# 10-M2_GPS.net
KiCad netlist of a schematic drawn in Altium Designer
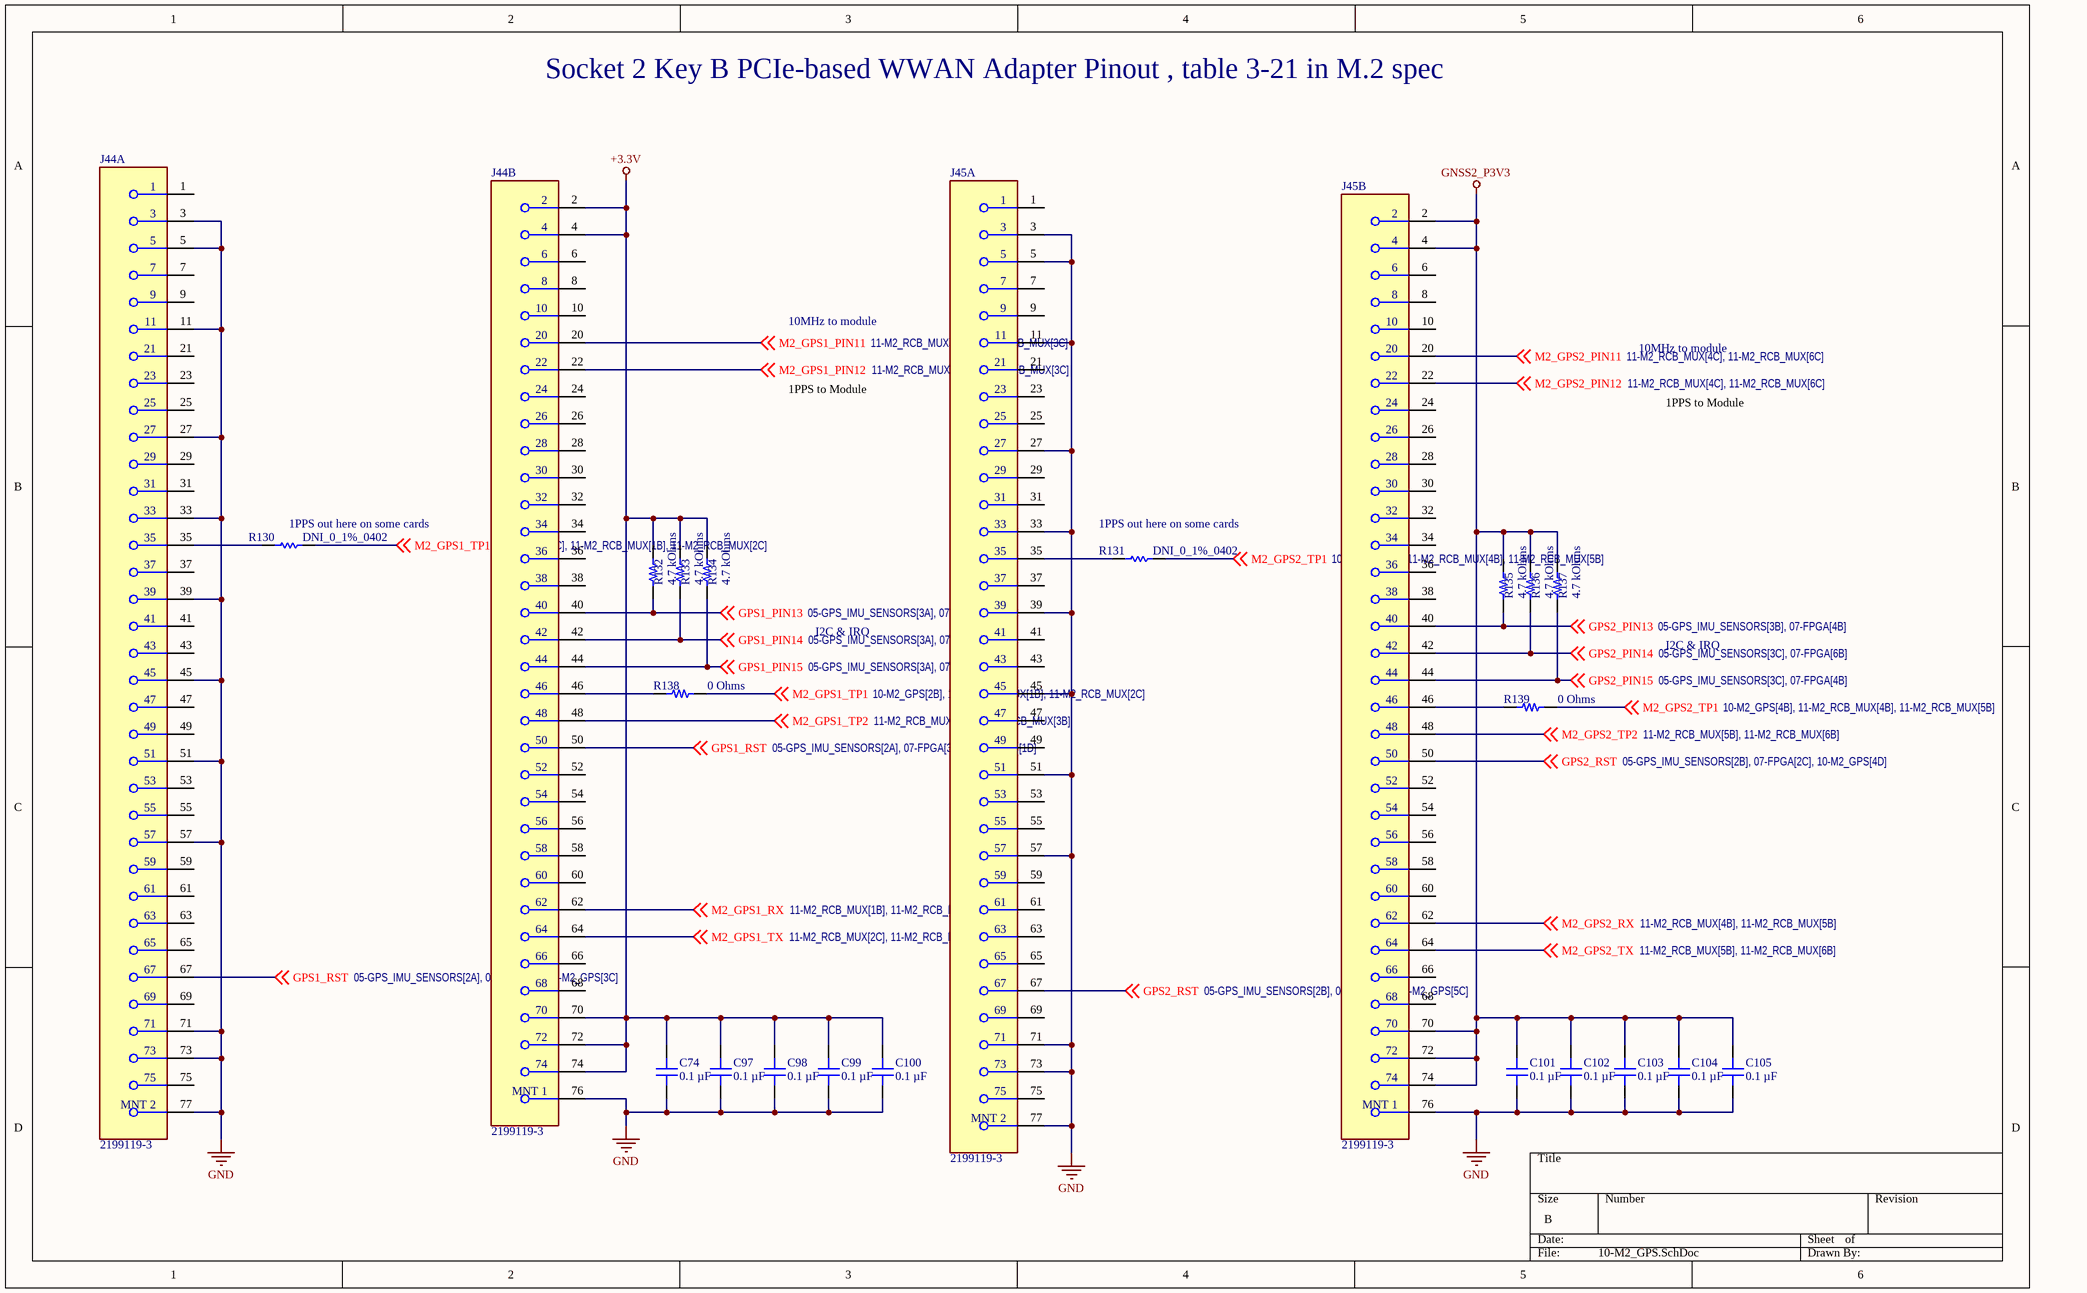
[diagram p0: 10-M2_GPS.SchDoc]

(export (version "E")
  (design (tool "Eeschema 10.0.6"))
  (components
    (comp (ref "C74")
      (value "0.1 µF")
      (footprint "CAP 0402_1005")
      (description "CAP CER 0.1UF 50V X7R 0402")
      (fields (field (name "TOLERANCE") "±10%") (field (name "PART NUMBER") "CC0402KRX7R9BB104"))
      (libsource (lib "Celestial Altium Library - altium_library") (part "Capacitor"))
    )
    (comp (ref "C97")
      (value "0.1 µF")
      (footprint "CAP 0402_1005")
      (description "CAP CER 0.1UF 50V X7R 0402")
      (fields (field (name "TOLERANCE") "±10%") (field (name "PART NUMBER") "CC0402KRX7R9BB104"))
      (libsource (lib "Celestial Altium Library - altium_library") (part "Capacitor"))
    )
    (comp (ref "C98")
      (value "0.1 µF")
      (footprint "CAP 0402_1005")
      (description "CAP CER 0.1UF 50V X7R 0402")
      (fields (field (name "TOLERANCE") "±10%") (field (name "PART NUMBER") "CC0402KRX7R9BB104"))
      (libsource (lib "Celestial Altium Library - altium_library") (part "Capacitor"))
    )
    (comp (ref "C99")
      (value "0.1 µF")
      (footprint "CAP 0402_1005")
      (description "CAP CER 0.1UF 50V X7R 0402")
      (fields (field (name "TOLERANCE") "±10%") (field (name "PART NUMBER") "CC0402KRX7R9BB104"))
      (libsource (lib "Celestial Altium Library - altium_library") (part "Capacitor"))
    )
    (comp (ref "C100")
      (value "0.1 µF")
      (footprint "CAP 0402_1005")
      (description "CAP CER 0.1UF 50V X7R 0402")
      (fields (field (name "TOLERANCE") "±10%") (field (name "PART NUMBER") "CC0402KRX7R9BB104"))
      (libsource (lib "Celestial Altium Library - altium_library") (part "Capacitor"))
    )
    (comp (ref "C101")
      (value "0.1 µF")
      (footprint "CAP 0402_1005")
      (description "CAP CER 0.1UF 50V X7R 0402")
      (fields (field (name "TOLERANCE") "±10%") (field (name "PART NUMBER") "CC0402KRX7R9BB104"))
      (libsource (lib "Celestial Altium Library - altium_library") (part "Capacitor"))
    )
    (comp (ref "C102")
      (value "0.1 µF")
      (footprint "CAP 0402_1005")
      (description "CAP CER 0.1UF 50V X7R 0402")
      (fields (field (name "TOLERANCE") "±10%") (field (name "PART NUMBER") "CC0402KRX7R9BB104"))
      (libsource (lib "Celestial Altium Library - altium_library") (part "Capacitor"))
    )
    (comp (ref "C103")
      (value "0.1 µF")
      (footprint "CAP 0402_1005")
      (description "CAP CER 0.1UF 50V X7R 0402")
      (fields (field (name "TOLERANCE") "±10%") (field (name "PART NUMBER") "CC0402KRX7R9BB104"))
      (libsource (lib "Celestial Altium Library - altium_library") (part "Capacitor"))
    )
    (comp (ref "C104")
      (value "0.1 µF")
      (footprint "CAP 0402_1005")
      (description "CAP CER 0.1UF 50V X7R 0402")
      (fields (field (name "TOLERANCE") "±10%") (field (name "PART NUMBER") "CC0402KRX7R9BB104"))
      (libsource (lib "Celestial Altium Library - altium_library") (part "Capacitor"))
    )
    (comp (ref "C105")
      (value "0.1 µF")
      (footprint "CAP 0402_1005")
      (description "CAP CER 0.1UF 50V X7R 0402")
      (fields (field (name "TOLERANCE") "±10%") (field (name "PART NUMBER") "CC0402KRX7R9BB104"))
      (libsource (lib "Celestial Altium Library - altium_library") (part "Capacitor"))
    )
    (comp (ref "J44")
      (value "2199119-3")
      (footprint "FP-2199119-3-MFG")
      (description "CONN M.2 FEMALE 67POS 0.020 GOLD")
      (libsource (lib "Altium Content Vault") (part "a14843ccfa78e5d0b739856168502fb"))
    )
    (comp (ref "J45")
      (value "2199119-3")
      (footprint "FP-2199119-3-MFG")
      (description "CONN M.2 FEMALE 67POS 0.020 GOLD")
      (libsource (lib "Altium Content Vault") (part "a14843ccfa78e5d0b739856168502fb"))
    )
    (comp (ref "R130")
      (value "DNI_0_1%_0402")
      (footprint "RESC1005X40X25LL05T05")
      (description "Chip Resistor, 0 Ohm, 0.1 W, -55 to 155 degC, 0402 (1005 Metric), RoHS, Tape and Reel")
      (fields (field (name "MANUFACTURER") "Panasonic") (field (name "TOLERANCE") "5%"))
      (libsource (lib "Altium Content Vault") (part "RES-2"))
    )
    (comp (ref "R131")
      (value "DNI_0_1%_0402")
      (footprint "RESC1005X40X25LL05T05")
      (description "Chip Resistor, 0 Ohm, 0.1 W, -55 to 155 degC, 0402 (1005 Metric), RoHS, Tape and Reel")
      (fields (field (name "MANUFACTURER") "Panasonic") (field (name "TOLERANCE") "5%"))
      (libsource (lib "Altium Content Vault") (part "RES-2"))
    )
    (comp (ref "R132")
      (value "4.7 kOhms")
      (footprint "YAGEO RES 0402_1005")
      (description "RES 4.7K OHM 1% 1/16W 0402")
      (fields (field (name "MANUFACTURER") "Yageo") (field (name "PART NUMBER") "RC0402FR-074K7L"))
      (libsource (lib "Celestial Altium Library - altium_library") (part "Resistor"))
    )
    (comp (ref "R133")
      (value "4.7 kOhms")
      (footprint "YAGEO RES 0402_1005")
      (description "RES 4.7K OHM 1% 1/16W 0402")
      (fields (field (name "MANUFACTURER") "Yageo") (field (name "PART NUMBER") "RC0402FR-074K7L"))
      (libsource (lib "Celestial Altium Library - altium_library") (part "Resistor"))
    )
    (comp (ref "R134")
      (value "4.7 kOhms")
      (footprint "YAGEO RES 0402_1005")
      (description "RES 4.7K OHM 1% 1/16W 0402")
      (fields (field (name "MANUFACTURER") "Yageo") (field (name "PART NUMBER") "RC0402FR-074K7L"))
      (libsource (lib "Celestial Altium Library - altium_library") (part "Resistor"))
    )
    (comp (ref "R135")
      (value "4.7 kOhms")
      (footprint "YAGEO RES 0402_1005")
      (description "RES 4.7K OHM 1% 1/16W 0402")
      (fields (field (name "MANUFACTURER") "Yageo") (field (name "PART NUMBER") "RC0402FR-074K7L"))
      (libsource (lib "Celestial Altium Library - altium_library") (part "Resistor"))
    )
    (comp (ref "R136")
      (value "4.7 kOhms")
      (footprint "YAGEO RES 0402_1005")
      (description "RES 4.7K OHM 1% 1/16W 0402")
      (fields (field (name "MANUFACTURER") "Yageo") (field (name "PART NUMBER") "RC0402FR-074K7L"))
      (libsource (lib "Celestial Altium Library - altium_library") (part "Resistor"))
    )
    (comp (ref "R137")
      (value "4.7 kOhms")
      (footprint "YAGEO RES 0402_1005")
      (description "RES 4.7K OHM 1% 1/16W 0402")
      (fields (field (name "MANUFACTURER") "Yageo") (field (name "PART NUMBER") "RC0402FR-074K7L"))
      (libsource (lib "Celestial Altium Library - altium_library") (part "Resistor"))
    )
    (comp (ref "R138")
      (value "0 Ohms")
      (footprint "YAGEO RES 0402_1005")
      (description "RES 0 OHM JUMPER 1/16W 0402")
      (fields (field (name "MANUFACTURER") "Yageo") (field (name "TOLERANCE") "Jumper"))
      (libsource (lib "Celestial Altium Library - altium_library") (part "Resistor"))
    )
    (comp (ref "R139")
      (value "0 Ohms")
      (footprint "YAGEO RES 0402_1005")
      (description "RES 0 OHM JUMPER 1/16W 0402")
      (fields (field (name "MANUFACTURER") "Yageo") (field (name "TOLERANCE") "Jumper"))
      (libsource (lib "Celestial Altium Library - altium_library") (part "Resistor"))
    )
  )
  (nets
    (net (code "1") (name "+3.3V") (class "Default")
      (node (ref "C100") (pin "1") (pinfunction "1_1") (pintype "passive"))
      (node (ref "C74") (pin "1") (pinfunction "1_1") (pintype "passive"))
      (node (ref "C97") (pin "1") (pinfunction "1_1") (pintype "passive"))
      (node (ref "C98") (pin "1") (pinfunction "1_1") (pintype "passive"))
      (node (ref "C99") (pin "1") (pinfunction "1_1") (pintype "passive"))
      (node (ref "J44") (pin "2") (pinfunction "2_2") (pintype "passive"))
      (node (ref "J44") (pin "4") (pinfunction "4_4") (pintype "passive"))
      (node (ref "J44") (pin "70") (pinfunction "70_70") (pintype "passive"))
      (node (ref "J44") (pin "72") (pinfunction "72_72") (pintype "passive"))
      (node (ref "J44") (pin "74") (pinfunction "74_74") (pintype "passive"))
      (node (ref "R132") (pin "2") (pinfunction "2_2") (pintype "passive"))
      (node (ref "R133") (pin "2") (pinfunction "2_2") (pintype "passive"))
      (node (ref "R134") (pin "2") (pinfunction "2_2") (pintype "passive"))
    )
    (net (code "2") (name "GND") (class "Default")
      (node (ref "C100") (pin "2") (pinfunction "2_2") (pintype "passive"))
      (node (ref "C101") (pin "2") (pinfunction "2_2") (pintype "passive"))
      (node (ref "C102") (pin "2") (pinfunction "2_2") (pintype "passive"))
      (node (ref "C103") (pin "2") (pinfunction "2_2") (pintype "passive"))
      (node (ref "C104") (pin "2") (pinfunction "2_2") (pintype "passive"))
      (node (ref "C105") (pin "2") (pinfunction "2_2") (pintype "passive"))
      (node (ref "C74") (pin "2") (pinfunction "2_2") (pintype "passive"))
      (node (ref "C97") (pin "2") (pinfunction "2_2") (pintype "passive"))
      (node (ref "C98") (pin "2") (pinfunction "2_2") (pintype "passive"))
      (node (ref "C99") (pin "2") (pinfunction "2_2") (pintype "passive"))
      (node (ref "J44") (pin "11") (pinfunction "11_11") (pintype "passive"))
      (node (ref "J44") (pin "27") (pinfunction "27_27") (pintype "passive"))
      (node (ref "J44") (pin "3") (pinfunction "3_3") (pintype "passive"))
      (node (ref "J44") (pin "33") (pinfunction "33_33") (pintype "passive"))
      (node (ref "J44") (pin "39") (pinfunction "39_39") (pintype "passive"))
      (node (ref "J44") (pin "45") (pinfunction "45_45") (pintype "passive"))
      (node (ref "J44") (pin "5") (pinfunction "5_5") (pintype "passive"))
      (node (ref "J44") (pin "51") (pinfunction "51_51") (pintype "passive"))
      (node (ref "J44") (pin "57") (pinfunction "57_57") (pintype "passive"))
      (node (ref "J44") (pin "71") (pinfunction "71_71") (pintype "passive"))
      (node (ref "J44") (pin "73") (pinfunction "73_73") (pintype "passive"))
      (node (ref "J44") (pin "76") (pinfunction "MNT_1_76") (pintype "passive"))
      (node (ref "J44") (pin "77") (pinfunction "MNT_2_77") (pintype "passive"))
      (node (ref "J45") (pin "11") (pinfunction "11_11") (pintype "passive"))
      (node (ref "J45") (pin "27") (pinfunction "27_27") (pintype "passive"))
      (node (ref "J45") (pin "3") (pinfunction "3_3") (pintype "passive"))
      (node (ref "J45") (pin "33") (pinfunction "33_33") (pintype "passive"))
      (node (ref "J45") (pin "39") (pinfunction "39_39") (pintype "passive"))
      (node (ref "J45") (pin "45") (pinfunction "45_45") (pintype "passive"))
      (node (ref "J45") (pin "5") (pinfunction "5_5") (pintype "passive"))
      (node (ref "J45") (pin "51") (pinfunction "51_51") (pintype "passive"))
      (node (ref "J45") (pin "57") (pinfunction "57_57") (pintype "passive"))
      (node (ref "J45") (pin "71") (pinfunction "71_71") (pintype "passive"))
      (node (ref "J45") (pin "73") (pinfunction "73_73") (pintype "passive"))
      (node (ref "J45") (pin "76") (pinfunction "MNT_1_76") (pintype "passive"))
      (node (ref "J45") (pin "77") (pinfunction "MNT_2_77") (pintype "passive"))
    )
    (net (code "3") (name "GNSS2_P3V3") (class "Default")
      (node (ref "C101") (pin "1") (pinfunction "1_1") (pintype "passive"))
      (node (ref "C102") (pin "1") (pinfunction "1_1") (pintype "passive"))
      (node (ref "C103") (pin "1") (pinfunction "1_1") (pintype "passive"))
      (node (ref "C104") (pin "1") (pinfunction "1_1") (pintype "passive"))
      (node (ref "C105") (pin "1") (pinfunction "1_1") (pintype "passive"))
      (node (ref "J45") (pin "2") (pinfunction "2_2") (pintype "passive"))
      (node (ref "J45") (pin "4") (pinfunction "4_4") (pintype "passive"))
      (node (ref "J45") (pin "70") (pinfunction "70_70") (pintype "passive"))
      (node (ref "J45") (pin "72") (pinfunction "72_72") (pintype "passive"))
      (node (ref "J45") (pin "74") (pinfunction "74_74") (pintype "passive"))
      (node (ref "R135") (pin "2") (pinfunction "2_2") (pintype "passive"))
      (node (ref "R136") (pin "2") (pinfunction "2_2") (pintype "passive"))
      (node (ref "R137") (pin "2") (pinfunction "2_2") (pintype "passive"))
    )
    (net (code "4") (name "GPS1_PIN13") (class "Default")
      (node (ref "J44") (pin "40") (pinfunction "40_40") (pintype "passive"))
      (node (ref "R132") (pin "1") (pinfunction "1_1") (pintype "passive"))
    )
    (net (code "5") (name "GPS1_PIN14") (class "Default")
      (node (ref "J44") (pin "42") (pinfunction "42_42") (pintype "passive"))
      (node (ref "R133") (pin "1") (pinfunction "1_1") (pintype "passive"))
    )
    (net (code "6") (name "GPS1_PIN15") (class "Default")
      (node (ref "J44") (pin "44") (pinfunction "44_44") (pintype "passive"))
      (node (ref "R134") (pin "1") (pinfunction "1_1") (pintype "passive"))
    )
    (net (code "7") (name "GPS1_RST") (class "Default")
      (node (ref "J44") (pin "50") (pinfunction "50_50") (pintype "passive"))
      (node (ref "J44") (pin "67") (pinfunction "67_67") (pintype "passive"))
    )
    (net (code "8") (name "GPS2_PIN13") (class "Default")
      (node (ref "J45") (pin "40") (pinfunction "40_40") (pintype "passive"))
      (node (ref "R135") (pin "1") (pinfunction "1_1") (pintype "passive"))
    )
    (net (code "9") (name "GPS2_PIN14") (class "Default")
      (node (ref "J45") (pin "42") (pinfunction "42_42") (pintype "passive"))
      (node (ref "R136") (pin "1") (pinfunction "1_1") (pintype "passive"))
    )
    (net (code "10") (name "GPS2_PIN15") (class "Default")
      (node (ref "J45") (pin "44") (pinfunction "44_44") (pintype "passive"))
      (node (ref "R137") (pin "1") (pinfunction "1_1") (pintype "passive"))
    )
    (net (code "11") (name "GPS2_RST") (class "Default")
      (node (ref "J45") (pin "50") (pinfunction "50_50") (pintype "passive"))
      (node (ref "J45") (pin "67") (pinfunction "67_67") (pintype "passive"))
    )
    (net (code "12") (name "M2_GPS1_PIN11") (class "Default")
      (node (ref "J44") (pin "20") (pinfunction "20_20") (pintype "passive"))
    )
    (net (code "13") (name "M2_GPS1_PIN12") (class "Default")
      (node (ref "J44") (pin "22") (pinfunction "22_22") (pintype "passive"))
    )
    (net (code "14") (name "M2_GPS1_RX") (class "Default")
      (node (ref "J44") (pin "62") (pinfunction "62_62") (pintype "passive"))
    )
    (net (code "15") (name "M2_GPS1_TP1") (class "Default")
      (node (ref "R130") (pin "2") (pinfunction "2_2") (pintype "passive"))
      (node (ref "R138") (pin "2") (pinfunction "2_2") (pintype "passive"))
    )
    (net (code "16") (name "M2_GPS1_TP2") (class "Default")
      (node (ref "J44") (pin "48") (pinfunction "48_48") (pintype "passive"))
    )
    (net (code "17") (name "M2_GPS1_TX") (class "Default")
      (node (ref "J44") (pin "64") (pinfunction "64_64") (pintype "passive"))
    )
    (net (code "18") (name "M2_GPS2_PIN11") (class "Default")
      (node (ref "J45") (pin "20") (pinfunction "20_20") (pintype "passive"))
    )
    (net (code "19") (name "M2_GPS2_PIN12") (class "Default")
      (node (ref "J45") (pin "22") (pinfunction "22_22") (pintype "passive"))
    )
    (net (code "20") (name "M2_GPS2_RX") (class "Default")
      (node (ref "J45") (pin "62") (pinfunction "62_62") (pintype "passive"))
    )
    (net (code "21") (name "M2_GPS2_TP1") (class "Default")
      (node (ref "R131") (pin "2") (pinfunction "2_2") (pintype "passive"))
      (node (ref "R139") (pin "2") (pinfunction "2_2") (pintype "passive"))
    )
    (net (code "22") (name "M2_GPS2_TP2") (class "Default")
      (node (ref "J45") (pin "48") (pinfunction "48_48") (pintype "passive"))
    )
    (net (code "23") (name "M2_GPS2_TX") (class "Default")
      (node (ref "J45") (pin "64") (pinfunction "64_64") (pintype "passive"))
    )
    (net (code "24") (name "Net-(J44-Pad35)") (class "Default")
      (node (ref "J44") (pin "35") (pinfunction "35_35") (pintype "passive"))
      (node (ref "R130") (pin "1") (pinfunction "1_1") (pintype "passive"))
    )
    (net (code "25") (name "Net-(J44-Pad46)") (class "Default")
      (node (ref "J44") (pin "46") (pinfunction "46_46") (pintype "passive"))
      (node (ref "R138") (pin "1") (pinfunction "1_1") (pintype "passive"))
    )
    (net (code "26") (name "Net-(J45-Pad35)") (class "Default")
      (node (ref "J45") (pin "35") (pinfunction "35_35") (pintype "passive"))
      (node (ref "R131") (pin "1") (pinfunction "1_1") (pintype "passive"))
    )
    (net (code "27") (name "Net-(J45-Pad46)") (class "Default")
      (node (ref "J45") (pin "46") (pinfunction "46_46") (pintype "passive"))
      (node (ref "R139") (pin "1") (pinfunction "1_1") (pintype "passive"))
    )
    (net (code "28") (name "unconnected-(J44-Pad1)") (class "Default")
      (node (ref "J44") (pin "1") (pinfunction "1_1") (pintype "passive"))
    )
    (net (code "29") (name "unconnected-(J44-Pad6)") (class "Default")
      (node (ref "J44") (pin "6") (pinfunction "6_6") (pintype "passive"))
    )
    (net (code "30") (name "unconnected-(J44-Pad7)") (class "Default")
      (node (ref "J44") (pin "7") (pinfunction "7_7") (pintype "passive"))
    )
    (net (code "31") (name "unconnected-(J44-Pad8)") (class "Default")
      (node (ref "J44") (pin "8") (pinfunction "8_8") (pintype "passive"))
    )
    (net (code "32") (name "unconnected-(J44-Pad9)") (class "Default")
      (node (ref "J44") (pin "9") (pinfunction "9_9") (pintype "passive"))
    )
    (net (code "33") (name "unconnected-(J44-Pad10)") (class "Default")
      (node (ref "J44") (pin "10") (pinfunction "10_10") (pintype "passive"))
    )
    (net (code "34") (name "unconnected-(J44-Pad21)") (class "Default")
      (node (ref "J44") (pin "21") (pinfunction "21_21") (pintype "passive"))
    )
    (net (code "35") (name "unconnected-(J44-Pad23)") (class "Default")
      (node (ref "J44") (pin "23") (pinfunction "23_23") (pintype "passive"))
    )
    (net (code "36") (name "unconnected-(J44-Pad24)") (class "Default")
      (node (ref "J44") (pin "24") (pinfunction "24_24") (pintype "passive"))
    )
    (net (code "37") (name "unconnected-(J44-Pad25)") (class "Default")
      (node (ref "J44") (pin "25") (pinfunction "25_25") (pintype "passive"))
    )
    (net (code "38") (name "unconnected-(J44-Pad26)") (class "Default")
      (node (ref "J44") (pin "26") (pinfunction "26_26") (pintype "passive"))
    )
    (net (code "39") (name "unconnected-(J44-Pad28)") (class "Default")
      (node (ref "J44") (pin "28") (pinfunction "28_28") (pintype "passive"))
    )
    (net (code "40") (name "unconnected-(J44-Pad29)") (class "Default")
      (node (ref "J44") (pin "29") (pinfunction "29_29") (pintype "passive"))
    )
    (net (code "41") (name "unconnected-(J44-Pad30)") (class "Default")
      (node (ref "J44") (pin "30") (pinfunction "30_30") (pintype "passive"))
    )
    (net (code "42") (name "unconnected-(J44-Pad31)") (class "Default")
      (node (ref "J44") (pin "31") (pinfunction "31_31") (pintype "passive"))
    )
    (net (code "43") (name "unconnected-(J44-Pad32)") (class "Default")
      (node (ref "J44") (pin "32") (pinfunction "32_32") (pintype "passive"))
    )
    (net (code "44") (name "unconnected-(J44-Pad34)") (class "Default")
      (node (ref "J44") (pin "34") (pinfunction "34_34") (pintype "passive"))
    )
    (net (code "45") (name "unconnected-(J44-Pad36)") (class "Default")
      (node (ref "J44") (pin "36") (pinfunction "36_36") (pintype "passive"))
    )
    (net (code "46") (name "unconnected-(J44-Pad37)") (class "Default")
      (node (ref "J44") (pin "37") (pinfunction "37_37") (pintype "passive"))
    )
    (net (code "47") (name "unconnected-(J44-Pad38)") (class "Default")
      (node (ref "J44") (pin "38") (pinfunction "38_38") (pintype "passive"))
    )
    (net (code "48") (name "unconnected-(J44-Pad41)") (class "Default")
      (node (ref "J44") (pin "41") (pinfunction "41_41") (pintype "passive"))
    )
    (net (code "49") (name "unconnected-(J44-Pad43)") (class "Default")
      (node (ref "J44") (pin "43") (pinfunction "43_43") (pintype "passive"))
    )
    (net (code "50") (name "unconnected-(J44-Pad47)") (class "Default")
      (node (ref "J44") (pin "47") (pinfunction "47_47") (pintype "passive"))
    )
    (net (code "51") (name "unconnected-(J44-Pad49)") (class "Default")
      (node (ref "J44") (pin "49") (pinfunction "49_49") (pintype "passive"))
    )
    (net (code "52") (name "unconnected-(J44-Pad52)") (class "Default")
      (node (ref "J44") (pin "52") (pinfunction "52_52") (pintype "passive"))
    )
    (net (code "53") (name "unconnected-(J44-Pad53)") (class "Default")
      (node (ref "J44") (pin "53") (pinfunction "53_53") (pintype "passive"))
    )
    (net (code "54") (name "unconnected-(J44-Pad54)") (class "Default")
      (node (ref "J44") (pin "54") (pinfunction "54_54") (pintype "passive"))
    )
    (net (code "55") (name "unconnected-(J44-Pad55)") (class "Default")
      (node (ref "J44") (pin "55") (pinfunction "55_55") (pintype "passive"))
    )
    (net (code "56") (name "unconnected-(J44-Pad56)") (class "Default")
      (node (ref "J44") (pin "56") (pinfunction "56_56") (pintype "passive"))
    )
    (net (code "57") (name "unconnected-(J44-Pad58)") (class "Default")
      (node (ref "J44") (pin "58") (pinfunction "58_58") (pintype "passive"))
    )
    (net (code "58") (name "unconnected-(J44-Pad59)") (class "Default")
      (node (ref "J44") (pin "59") (pinfunction "59_59") (pintype "passive"))
    )
    (net (code "59") (name "unconnected-(J44-Pad60)") (class "Default")
      (node (ref "J44") (pin "60") (pinfunction "60_60") (pintype "passive"))
    )
    (net (code "60") (name "unconnected-(J44-Pad61)") (class "Default")
      (node (ref "J44") (pin "61") (pinfunction "61_61") (pintype "passive"))
    )
    (net (code "61") (name "unconnected-(J44-Pad63)") (class "Default")
      (node (ref "J44") (pin "63") (pinfunction "63_63") (pintype "passive"))
    )
    (net (code "62") (name "unconnected-(J44-Pad65)") (class "Default")
      (node (ref "J44") (pin "65") (pinfunction "65_65") (pintype "passive"))
    )
    (net (code "63") (name "unconnected-(J44-Pad66)") (class "Default")
      (node (ref "J44") (pin "66") (pinfunction "66_66") (pintype "passive"))
    )
    (net (code "64") (name "unconnected-(J44-Pad68)") (class "Default")
      (node (ref "J44") (pin "68") (pinfunction "68_68") (pintype "passive"))
    )
    (net (code "65") (name "unconnected-(J44-Pad69)") (class "Default")
      (node (ref "J44") (pin "69") (pinfunction "69_69") (pintype "passive"))
    )
    (net (code "66") (name "unconnected-(J44-Pad75)") (class "Default")
      (node (ref "J44") (pin "75") (pinfunction "75_75") (pintype "passive"))
    )
    (net (code "67") (name "unconnected-(J45-Pad1)") (class "Default")
      (node (ref "J45") (pin "1") (pinfunction "1_1") (pintype "passive"))
    )
    (net (code "68") (name "unconnected-(J45-Pad6)") (class "Default")
      (node (ref "J45") (pin "6") (pinfunction "6_6") (pintype "passive"))
    )
    (net (code "69") (name "unconnected-(J45-Pad7)") (class "Default")
      (node (ref "J45") (pin "7") (pinfunction "7_7") (pintype "passive"))
    )
    (net (code "70") (name "unconnected-(J45-Pad8)") (class "Default")
      (node (ref "J45") (pin "8") (pinfunction "8_8") (pintype "passive"))
    )
    (net (code "71") (name "unconnected-(J45-Pad9)") (class "Default")
      (node (ref "J45") (pin "9") (pinfunction "9_9") (pintype "passive"))
    )
    (net (code "72") (name "unconnected-(J45-Pad10)") (class "Default")
      (node (ref "J45") (pin "10") (pinfunction "10_10") (pintype "passive"))
    )
    (net (code "73") (name "unconnected-(J45-Pad21)") (class "Default")
      (node (ref "J45") (pin "21") (pinfunction "21_21") (pintype "passive"))
    )
    (net (code "74") (name "unconnected-(J45-Pad23)") (class "Default")
      (node (ref "J45") (pin "23") (pinfunction "23_23") (pintype "passive"))
    )
    (net (code "75") (name "unconnected-(J45-Pad24)") (class "Default")
      (node (ref "J45") (pin "24") (pinfunction "24_24") (pintype "passive"))
    )
    (net (code "76") (name "unconnected-(J45-Pad25)") (class "Default")
      (node (ref "J45") (pin "25") (pinfunction "25_25") (pintype "passive"))
    )
    (net (code "77") (name "unconnected-(J45-Pad26)") (class "Default")
      (node (ref "J45") (pin "26") (pinfunction "26_26") (pintype "passive"))
    )
    (net (code "78") (name "unconnected-(J45-Pad28)") (class "Default")
      (node (ref "J45") (pin "28") (pinfunction "28_28") (pintype "passive"))
    )
    (net (code "79") (name "unconnected-(J45-Pad29)") (class "Default")
      (node (ref "J45") (pin "29") (pinfunction "29_29") (pintype "passive"))
    )
    (net (code "80") (name "unconnected-(J45-Pad30)") (class "Default")
      (node (ref "J45") (pin "30") (pinfunction "30_30") (pintype "passive"))
    )
    (net (code "81") (name "unconnected-(J45-Pad31)") (class "Default")
      (node (ref "J45") (pin "31") (pinfunction "31_31") (pintype "passive"))
    )
    (net (code "82") (name "unconnected-(J45-Pad32)") (class "Default")
      (node (ref "J45") (pin "32") (pinfunction "32_32") (pintype "passive"))
    )
    (net (code "83") (name "unconnected-(J45-Pad34)") (class "Default")
      (node (ref "J45") (pin "34") (pinfunction "34_34") (pintype "passive"))
    )
    (net (code "84") (name "unconnected-(J45-Pad36)") (class "Default")
      (node (ref "J45") (pin "36") (pinfunction "36_36") (pintype "passive"))
    )
    (net (code "85") (name "unconnected-(J45-Pad37)") (class "Default")
      (node (ref "J45") (pin "37") (pinfunction "37_37") (pintype "passive"))
    )
    (net (code "86") (name "unconnected-(J45-Pad38)") (class "Default")
      (node (ref "J45") (pin "38") (pinfunction "38_38") (pintype "passive"))
    )
    (net (code "87") (name "unconnected-(J45-Pad41)") (class "Default")
      (node (ref "J45") (pin "41") (pinfunction "41_41") (pintype "passive"))
    )
    (net (code "88") (name "unconnected-(J45-Pad43)") (class "Default")
      (node (ref "J45") (pin "43") (pinfunction "43_43") (pintype "passive"))
    )
    (net (code "89") (name "unconnected-(J45-Pad47)") (class "Default")
      (node (ref "J45") (pin "47") (pinfunction "47_47") (pintype "passive"))
    )
    (net (code "90") (name "unconnected-(J45-Pad49)") (class "Default")
      (node (ref "J45") (pin "49") (pinfunction "49_49") (pintype "passive"))
    )
    (net (code "91") (name "unconnected-(J45-Pad52)") (class "Default")
      (node (ref "J45") (pin "52") (pinfunction "52_52") (pintype "passive"))
    )
    (net (code "92") (name "unconnected-(J45-Pad53)") (class "Default")
      (node (ref "J45") (pin "53") (pinfunction "53_53") (pintype "passive"))
    )
    (net (code "93") (name "unconnected-(J45-Pad54)") (class "Default")
      (node (ref "J45") (pin "54") (pinfunction "54_54") (pintype "passive"))
    )
    (net (code "94") (name "unconnected-(J45-Pad55)") (class "Default")
      (node (ref "J45") (pin "55") (pinfunction "55_55") (pintype "passive"))
    )
    (net (code "95") (name "unconnected-(J45-Pad56)") (class "Default")
      (node (ref "J45") (pin "56") (pinfunction "56_56") (pintype "passive"))
    )
    (net (code "96") (name "unconnected-(J45-Pad58)") (class "Default")
      (node (ref "J45") (pin "58") (pinfunction "58_58") (pintype "passive"))
    )
    (net (code "97") (name "unconnected-(J45-Pad59)") (class "Default")
      (node (ref "J45") (pin "59") (pinfunction "59_59") (pintype "passive"))
    )
    (net (code "98") (name "unconnected-(J45-Pad60)") (class "Default")
      (node (ref "J45") (pin "60") (pinfunction "60_60") (pintype "passive"))
    )
    (net (code "99") (name "unconnected-(J45-Pad61)") (class "Default")
      (node (ref "J45") (pin "61") (pinfunction "61_61") (pintype "passive"))
    )
    (net (code "100") (name "unconnected-(J45-Pad63)") (class "Default")
      (node (ref "J45") (pin "63") (pinfunction "63_63") (pintype "passive"))
    )
    (net (code "101") (name "unconnected-(J45-Pad65)") (class "Default")
      (node (ref "J45") (pin "65") (pinfunction "65_65") (pintype "passive"))
    )
    (net (code "102") (name "unconnected-(J45-Pad66)") (class "Default")
      (node (ref "J45") (pin "66") (pinfunction "66_66") (pintype "passive"))
    )
    (net (code "103") (name "unconnected-(J45-Pad68)") (class "Default")
      (node (ref "J45") (pin "68") (pinfunction "68_68") (pintype "passive"))
    )
    (net (code "104") (name "unconnected-(J45-Pad69)") (class "Default")
      (node (ref "J45") (pin "69") (pinfunction "69_69") (pintype "passive"))
    )
    (net (code "105") (name "unconnected-(J45-Pad75)") (class "Default")
      (node (ref "J45") (pin "75") (pinfunction "75_75") (pintype "passive"))
    )
  )
)
